# 00A-92.net
KiCad netlist of a schematic drawn in EAGLE
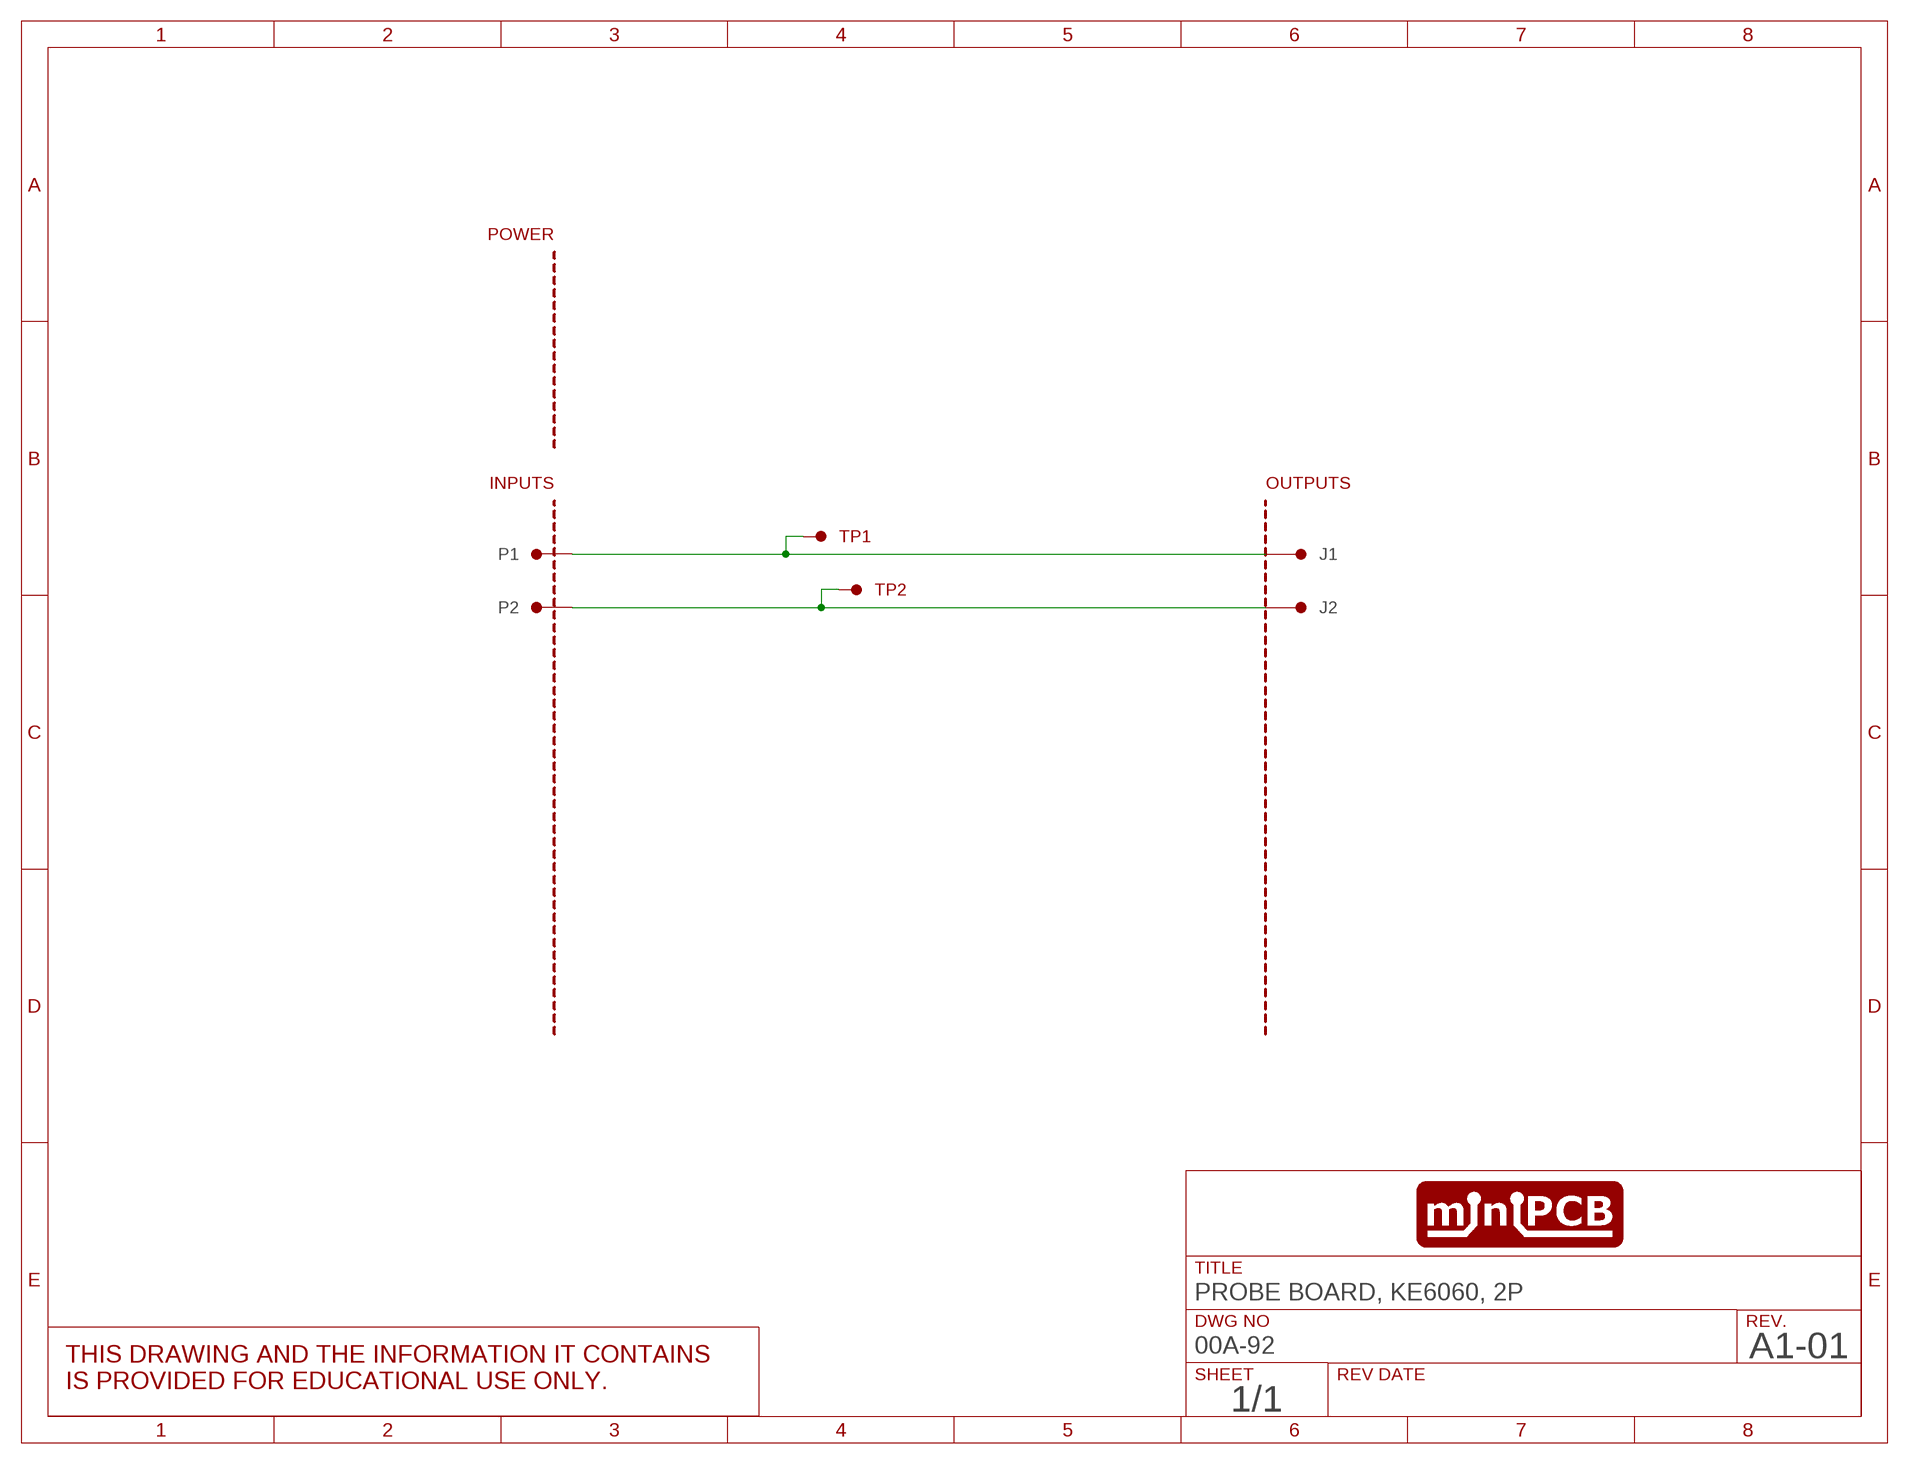
[diagram p0: schematic, sheet 1]

(export (version "E")
  (design (tool "Eeschema 10.0.6"))
  (components
    (comp (ref "J1")
      (value "PINS_1KE6060")
      (footprint "eagle-import:PINS_1_KE6060")
      (libsource (lib "eagle-import") (part "PINS_1KE6060"))
    )
    (comp (ref "J2")
      (value "PINS_1KE6060")
      (footprint "eagle-import:PINS_1_KE6060")
      (libsource (lib "eagle-import") (part "PINS_1KE6060"))
    )
    (comp (ref "P1")
      (value "PINS_124AWG-NOTEXT")
      (footprint "eagle-import:PINS_1_1MM-NOTEXT")
      (libsource (lib "eagle-import") (part "PINS_124AWG-NOTEXT"))
    )
    (comp (ref "P2")
      (value "PINS_124AWG-NOTEXT")
      (footprint "eagle-import:PINS_1_1MM-NOTEXT")
      (libsource (lib "eagle-import") (part "PINS_124AWG-NOTEXT"))
    )
    (comp (ref "PCB1")
      (value "MINIPCB_0P00A-20X33")
      (footprint "eagle-import:MINIPCB_00A_20X33")
      (fields (field (name "PART_NUMBER") "00A-92-A1-01"))
      (libsource (lib "eagle-import") (part "MINIPCB_0P00A-20X33"))
    )
    (comp (ref "TP1")
      (value "TESTPOINTKE5000-SMTEXT")
      (footprint "eagle-import:PINS_1_TESTPOINT_KE5000_NOTEXT")
      (libsource (lib "eagle-import") (part "TESTPOINTKE5000-SMTEXT"))
    )
    (comp (ref "TP2")
      (value "TESTPOINTKE5000-SMTEXT")
      (footprint "eagle-import:PINS_1_TESTPOINT_KE5000_NOTEXT")
      (libsource (lib "eagle-import") (part "TESTPOINTKE5000-SMTEXT"))
    )
  )
  (nets
    (net (code "1") (name "Net-(J1-1-Pad2)") (class "Default")
      (node (ref "J1") (pin "1") (pinfunction "1_1") (pintype "bidirectional"))
      (node (ref "J1") (pin "2") (pinfunction "1_2") (pintype "bidirectional"))
      (node (ref "P1") (pin "1") (pinfunction "1_1") (pintype "bidirectional"))
      (node (ref "P1") (pin "2") (pinfunction "1_2") (pintype "bidirectional"))
      (node (ref "TP1") (pin "1") (pinfunction "1_1") (pintype "bidirectional"))
    )
    (net (code "2") (name "Net-(J2-1-Pad2)") (class "Default")
      (node (ref "J2") (pin "1") (pinfunction "1_1") (pintype "bidirectional"))
      (node (ref "J2") (pin "2") (pinfunction "1_2") (pintype "bidirectional"))
      (node (ref "P2") (pin "1") (pinfunction "1_1") (pintype "bidirectional"))
      (node (ref "P2") (pin "2") (pinfunction "1_2") (pintype "bidirectional"))
      (node (ref "TP2") (pin "1") (pinfunction "1_1") (pintype "bidirectional"))
    )
  )
)
